# Power.net
KiCad netlist of a schematic drawn in Altium Designer
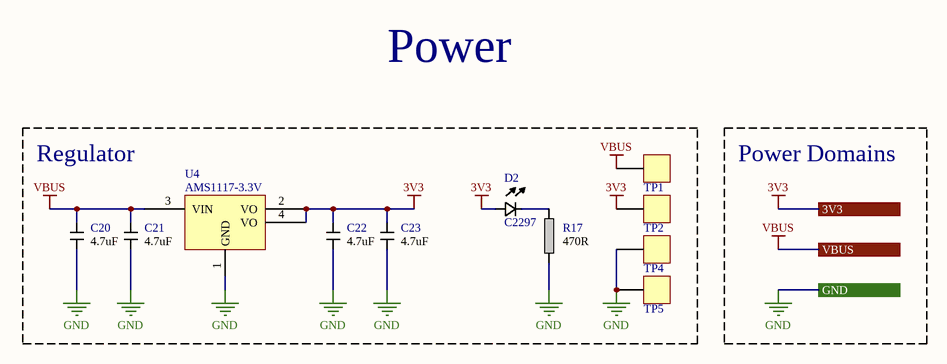
[diagram p0: Power.SchDoc]

(export (version "E")
  (design (tool "Eeschema 10.0.6"))
  (components
    (comp (ref "C20")
      (value "4.7uF")
      (footprint "0805")
      (description "35V 4.7uF X7R ±10% 0805  Multilayer Ceramic Capacitors MLCC - SMD/SMT ROHS")
      (fields
        (field (name "MANUFACTURER") "Samwha Capacitor")
        (field (name "MANUFACTURER PART NUMBER") "CS2012X7R475K350NRE")
      )
      (libsource (lib "Library") (part "CAP"))
    )
    (comp (ref "C21")
      (value "4.7uF")
      (footprint "0805")
      (description "35V 4.7uF X7R ±10% 0805  Multilayer Ceramic Capacitors MLCC - SMD/SMT ROHS")
      (fields
        (field (name "MANUFACTURER") "Samwha Capacitor")
        (field (name "MANUFACTURER PART NUMBER") "CS2012X7R475K350NRE")
      )
      (libsource (lib "Library") (part "CAP"))
    )
    (comp (ref "C22")
      (value "4.7uF")
      (footprint "0805")
      (description "35V 4.7uF X7R ±10% 0805  Multilayer Ceramic Capacitors MLCC - SMD/SMT ROHS")
      (fields
        (field (name "MANUFACTURER") "Samwha Capacitor")
        (field (name "MANUFACTURER PART NUMBER") "CS2012X7R475K350NRE")
      )
      (libsource (lib "Library") (part "CAP"))
    )
    (comp (ref "C23")
      (value "4.7uF")
      (footprint "0805")
      (description "35V 4.7uF X7R ±10% 0805  Multilayer Ceramic Capacitors MLCC - SMD/SMT ROHS")
      (fields
        (field (name "MANUFACTURER") "Samwha Capacitor")
        (field (name "MANUFACTURER PART NUMBER") "CS2012X7R475K350NRE")
      )
      (libsource (lib "Library") (part "CAP"))
    )
    (comp (ref "D2")
      (value "LED")
      (footprint "0805")
      (description "0805 Light Emitting Diodes (LED) ROHS")
      (fields
        (field (name "MANUFACTURER") "Hubei KENTO Elec")
        (field (name "MANUFACTURER PART NUMBER") "C2297")
      )
      (libsource (lib "Library") (part "LED"))
    )
    (comp (ref "R17")
      (value "470R")
      (footprint "0805")
      (description "125mW Thick Film Resistors ±1% 470Ω 0805  Chip Resistor - Surface Mount ROHS")
      (fields
        (field (name "MANUFACTURER") "UNI-ROYAL(Uniroyal Elec)")
        (field (name "MANUFACTURER PART NUMBER") "0805W8F4700T5E")
      )
      (libsource (lib "Library") (part "RES"))
    )
    (comp (ref "TP1")
      (value "5V")
      (footprint "5015")
      (description "Thimble/Copper Rod/Test Ring ROHS")
      (fields (field (name "MANUFACTURER") "Ronghe") (field (name "MANUFACTURER PART NUMBER") "RH-5015"))
      (libsource (lib "Library") (part "TESTPOINT_5015"))
    )
    (comp (ref "TP2")
      (value "3V3")
      (footprint "5015")
      (description "Thimble/Copper Rod/Test Ring ROHS")
      (fields (field (name "MANUFACTURER") "Ronghe") (field (name "MANUFACTURER PART NUMBER") "RH-5015"))
      (libsource (lib "Library") (part "TESTPOINT_5015"))
    )
    (comp (ref "TP4")
      (value "GND")
      (footprint "5015")
      (description "Thimble/Copper Rod/Test Ring ROHS")
      (fields (field (name "MANUFACTURER") "Ronghe") (field (name "MANUFACTURER PART NUMBER") "RH-5015"))
      (libsource (lib "Library") (part "TESTPOINT_5015"))
    )
    (comp (ref "TP5")
      (value "GND")
      (footprint "5015")
      (description "Thimble/Copper Rod/Test Ring ROHS")
      (fields (field (name "MANUFACTURER") "Ronghe") (field (name "MANUFACTURER PART NUMBER") "RH-5015"))
      (libsource (lib "Library") (part "TESTPOINT_5015"))
    )
    (comp (ref "U4")
      (value "AMS1117-3.3V")
      (footprint "SOT-223")
      (description "IC-1117 V.reg. 1A 3V3 SOT223 SMD Ams")
      (fields
        (field (name "MANUFACTURER") "Shenzhen Fuman Elec")
        (field (name "MANUFACTURER PART NUMBER") "AMS1117-3.3V")
      )
      (libsource (lib "Library") (part "AMS1117-3.3V"))
    )
  )
  (nets
    (net (code "1") (name "3V3") (class "Default")
      (node (ref "C22") (pin "1") (pintype "passive"))
      (node (ref "C23") (pin "1") (pintype "passive"))
      (node (ref "D2") (pin "1") (pinfunction "1_1") (pintype "passive"))
      (node (ref "TP2") (pin "1") (pinfunction "1_1") (pintype "passive"))
      (node (ref "U4") (pin "2") (pinfunction "VO_2") (pintype "passive"))
      (node (ref "U4") (pin "4") (pinfunction "VO_4") (pintype "passive"))
    )
    (net (code "2") (name "GND") (class "Default")
      (node (ref "C20") (pin "2") (pintype "passive"))
      (node (ref "C21") (pin "2") (pintype "passive"))
      (node (ref "C22") (pin "2") (pintype "passive"))
      (node (ref "C23") (pin "2") (pintype "passive"))
      (node (ref "R17") (pin "2") (pinfunction "2_2") (pintype "passive"))
      (node (ref "TP4") (pin "1") (pinfunction "1_1") (pintype "passive"))
      (node (ref "TP5") (pin "1") (pinfunction "1_1") (pintype "passive"))
      (node (ref "U4") (pin "1") (pinfunction "GND_1") (pintype "passive"))
    )
    (net (code "3") (name "Net-(D2-Pad2)") (class "Default")
      (node (ref "D2") (pin "2") (pinfunction "2_2") (pintype "passive"))
      (node (ref "R17") (pin "1") (pinfunction "1_1") (pintype "passive"))
    )
    (net (code "4") (name "VBUS") (class "Default")
      (node (ref "C20") (pin "1") (pintype "passive"))
      (node (ref "C21") (pin "1") (pintype "passive"))
      (node (ref "TP1") (pin "1") (pinfunction "1_1") (pintype "passive"))
      (node (ref "U4") (pin "3") (pinfunction "VIN_3") (pintype "passive"))
    )
  )
)
